# DDR.net
KiCad netlist of a schematic drawn in Altium Designer
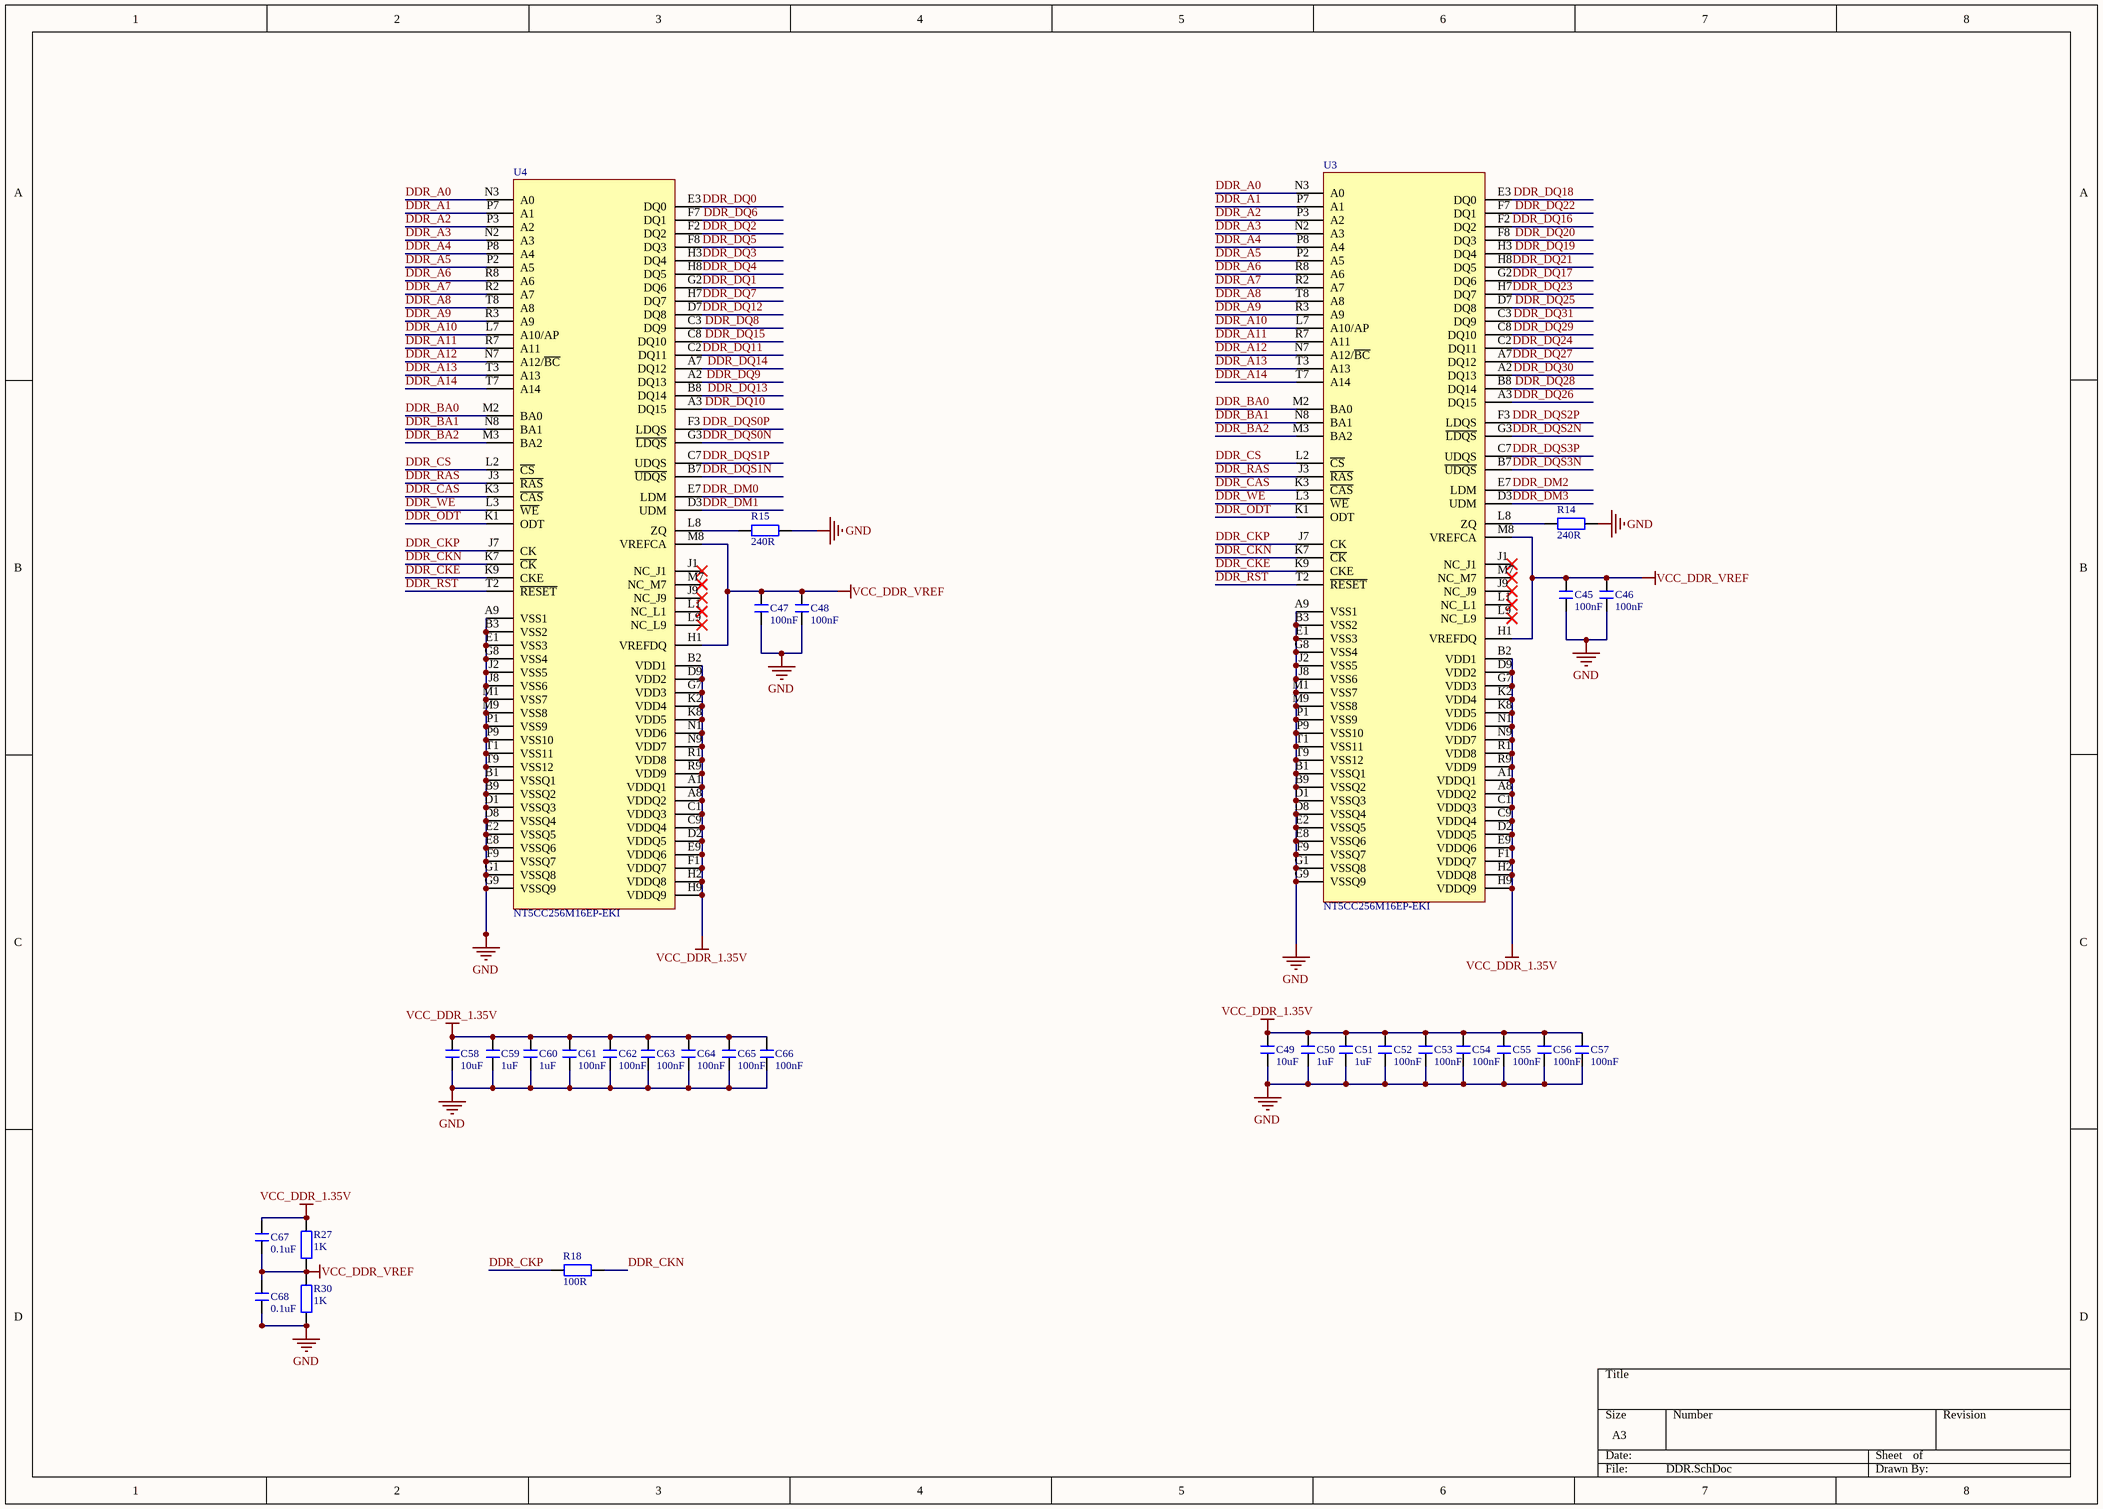
[diagram p0: DDR.SchDoc]

(export (version "E")
  (design (tool "Eeschema 10.0.6"))
  (components
    (comp (ref "C45")
      (value "100nF")
      (footprint "C 0402")
      (description "无极性贴片电容")
      (fields (field (name "版权归属") "正点原子"))
      (libsource (lib "20240511") (part "C"))
    )
    (comp (ref "C46")
      (value "100nF")
      (footprint "C 0402")
      (description "无极性贴片电容")
      (fields (field (name "版权归属") "正点原子"))
      (libsource (lib "20240511") (part "C"))
    )
    (comp (ref "C47")
      (value "100nF")
      (footprint "C 0402")
      (description "无极性贴片电容")
      (fields (field (name "版权归属") "正点原子"))
      (libsource (lib "20240511") (part "C"))
    )
    (comp (ref "C48")
      (value "100nF")
      (footprint "C 0402")
      (description "无极性贴片电容")
      (fields (field (name "版权归属") "正点原子"))
      (libsource (lib "20240511") (part "C"))
    )
    (comp (ref "C49")
      (value "10uF")
      (footprint "C 0603")
      (description "无极性贴片电容")
      (fields (field (name "版权归属") "正点原子"))
      (libsource (lib "20240511") (part "C"))
    )
    (comp (ref "C50")
      (value "1uF")
      (footprint "C 0402")
      (description "无极性贴片电容")
      (fields (field (name "版权归属") "正点原子"))
      (libsource (lib "20240511") (part "C"))
    )
    (comp (ref "C51")
      (value "1uF")
      (footprint "C 0402")
      (description "无极性贴片电容")
      (fields (field (name "版权归属") "正点原子"))
      (libsource (lib "20240511") (part "C"))
    )
    (comp (ref "C52")
      (value "100nF")
      (footprint "C 0402")
      (description "无极性贴片电容")
      (fields (field (name "版权归属") "正点原子"))
      (libsource (lib "20240511") (part "C"))
    )
    (comp (ref "C53")
      (value "100nF")
      (footprint "C 0402")
      (description "无极性贴片电容")
      (fields (field (name "版权归属") "正点原子"))
      (libsource (lib "20240511") (part "C"))
    )
    (comp (ref "C54")
      (value "100nF")
      (footprint "C 0402")
      (description "无极性贴片电容")
      (fields (field (name "版权归属") "正点原子"))
      (libsource (lib "20240511") (part "C"))
    )
    (comp (ref "C55")
      (value "100nF")
      (footprint "C 0402")
      (description "无极性贴片电容")
      (fields (field (name "版权归属") "正点原子"))
      (libsource (lib "20240511") (part "C"))
    )
    (comp (ref "C56")
      (value "100nF")
      (footprint "C 0402")
      (description "无极性贴片电容")
      (fields (field (name "版权归属") "正点原子"))
      (libsource (lib "20240511") (part "C"))
    )
    (comp (ref "C57")
      (value "100nF")
      (footprint "C 0402")
      (description "无极性贴片电容")
      (fields (field (name "版权归属") "正点原子"))
      (libsource (lib "20240511") (part "C"))
    )
    (comp (ref "C58")
      (value "10uF")
      (footprint "C 0603")
      (description "无极性贴片电容")
      (fields (field (name "版权归属") "正点原子"))
      (libsource (lib "20240511") (part "C"))
    )
    (comp (ref "C59")
      (value "1uF")
      (footprint "C 0402")
      (description "无极性贴片电容")
      (fields (field (name "版权归属") "正点原子"))
      (libsource (lib "20240511") (part "C"))
    )
    (comp (ref "C60")
      (value "1uF")
      (footprint "C 0402")
      (description "无极性贴片电容")
      (fields (field (name "版权归属") "正点原子"))
      (libsource (lib "20240511") (part "C"))
    )
    (comp (ref "C61")
      (value "100nF")
      (footprint "C 0402")
      (description "无极性贴片电容")
      (fields (field (name "版权归属") "正点原子"))
      (libsource (lib "20240511") (part "C"))
    )
    (comp (ref "C62")
      (value "100nF")
      (footprint "C 0402")
      (description "无极性贴片电容")
      (fields (field (name "版权归属") "正点原子"))
      (libsource (lib "20240511") (part "C"))
    )
    (comp (ref "C63")
      (value "100nF")
      (footprint "C 0402")
      (description "无极性贴片电容")
      (fields (field (name "版权归属") "正点原子"))
      (libsource (lib "20240511") (part "C"))
    )
    (comp (ref "C64")
      (value "100nF")
      (footprint "C 0402")
      (description "无极性贴片电容")
      (fields (field (name "版权归属") "正点原子"))
      (libsource (lib "20240511") (part "C"))
    )
    (comp (ref "C65")
      (value "100nF")
      (footprint "C 0402")
      (description "无极性贴片电容")
      (fields (field (name "版权归属") "正点原子"))
      (libsource (lib "20240511") (part "C"))
    )
    (comp (ref "C66")
      (value "100nF")
      (footprint "C 0402")
      (description "无极性贴片电容")
      (fields (field (name "版权归属") "正点原子"))
      (libsource (lib "20240511") (part "C"))
    )
    (comp (ref "C67")
      (value "0.1uF")
      (footprint "C 0402")
      (description "无极性贴片电容")
      (fields (field (name "版权归属") "正点原子"))
      (libsource (lib "20240511") (part "C"))
    )
    (comp (ref "C68")
      (value "0.1uF")
      (footprint "C 0402")
      (description "无极性贴片电容")
      (fields (field (name "版权归属") "正点原子"))
      (libsource (lib "20240511") (part "C"))
    )
    (comp (ref "R14")
      (value "240R")
      (footprint "R 0402")
      (description "贴片电阻")
      (fields (field (name "版权归属") "正点原子"))
      (libsource (lib "20240511") (part "R"))
    )
    (comp (ref "R15")
      (value "240R")
      (footprint "R 0402")
      (description "贴片电阻")
      (fields (field (name "版权归属") "正点原子"))
      (libsource (lib "20240511") (part "R"))
    )
    (comp (ref "R18")
      (value "100R")
      (footprint "R 0402")
      (description "贴片电阻")
      (fields (field (name "版权归属") "正点原子"))
      (libsource (lib "20240511") (part "R"))
    )
    (comp (ref "R27")
      (value "1K")
      (footprint "R 0402")
      (description "贴片电阻")
      (fields (field (name "版权归属") "正点原子"))
      (libsource (lib "20240511") (part "R"))
    )
    (comp (ref "R30")
      (value "1K")
      (footprint "R 0402")
      (description "贴片电阻")
      (fields (field (name "版权归属") "正点原子"))
      (libsource (lib "20240511") (part "R"))
    )
    (comp (ref "U3")
      (value "NT5CC256M16EP-EKI")
      (footprint "BGA96")
      (libsource (lib "20240511") (part "MT41K256M16TW"))
    )
    (comp (ref "U4")
      (value "NT5CC256M16EP-EKI")
      (footprint "BGA96")
      (libsource (lib "20240511") (part "MT41K256M16TW"))
    )
  )
  (nets
    (net (code "1") (name "/DDR_A0") (class "Default")
      (node (ref "U3") (pin "N3") (pinfunction "A0_N3") (pintype "passive"))
      (node (ref "U4") (pin "N3") (pinfunction "A0_N3") (pintype "passive"))
    )
    (net (code "2") (name "/DDR_A1") (class "Default")
      (node (ref "U3") (pin "P7") (pinfunction "A1_P7") (pintype "passive"))
      (node (ref "U4") (pin "P7") (pinfunction "A1_P7") (pintype "passive"))
    )
    (net (code "3") (name "/DDR_A2") (class "Default")
      (node (ref "U3") (pin "P3") (pinfunction "A2_P3") (pintype "passive"))
      (node (ref "U4") (pin "P3") (pinfunction "A2_P3") (pintype "passive"))
    )
    (net (code "4") (name "/DDR_A3") (class "Default")
      (node (ref "U3") (pin "N2") (pinfunction "A3_N2") (pintype "passive"))
      (node (ref "U4") (pin "N2") (pinfunction "A3_N2") (pintype "passive"))
    )
    (net (code "5") (name "/DDR_A4") (class "Default")
      (node (ref "U3") (pin "P8") (pinfunction "A4_P8") (pintype "passive"))
      (node (ref "U4") (pin "P8") (pinfunction "A4_P8") (pintype "passive"))
    )
    (net (code "6") (name "/DDR_A5") (class "Default")
      (node (ref "U3") (pin "P2") (pinfunction "A5_P2") (pintype "passive"))
      (node (ref "U4") (pin "P2") (pinfunction "A5_P2") (pintype "passive"))
    )
    (net (code "7") (name "/DDR_A6") (class "Default")
      (node (ref "U3") (pin "R8") (pinfunction "A6_R8") (pintype "passive"))
      (node (ref "U4") (pin "R8") (pinfunction "A6_R8") (pintype "passive"))
    )
    (net (code "8") (name "/DDR_A7") (class "Default")
      (node (ref "U3") (pin "R2") (pinfunction "A7_R2") (pintype "passive"))
      (node (ref "U4") (pin "R2") (pinfunction "A7_R2") (pintype "passive"))
    )
    (net (code "9") (name "/DDR_A8") (class "Default")
      (node (ref "U3") (pin "T8") (pinfunction "A8_T8") (pintype "passive"))
      (node (ref "U4") (pin "T8") (pinfunction "A8_T8") (pintype "passive"))
    )
    (net (code "10") (name "/DDR_A9") (class "Default")
      (node (ref "U3") (pin "R3") (pinfunction "A9_R3") (pintype "passive"))
      (node (ref "U4") (pin "R3") (pinfunction "A9_R3") (pintype "passive"))
    )
    (net (code "11") (name "/DDR_A10") (class "Default")
      (node (ref "U3") (pin "L7") (pinfunction "A10/AP_L7") (pintype "passive"))
      (node (ref "U4") (pin "L7") (pinfunction "A10/AP_L7") (pintype "passive"))
    )
    (net (code "12") (name "/DDR_A11") (class "Default")
      (node (ref "U3") (pin "R7") (pinfunction "A11_R7") (pintype "passive"))
      (node (ref "U4") (pin "R7") (pinfunction "A11_R7") (pintype "passive"))
    )
    (net (code "13") (name "/DDR_A12") (class "Default")
      (node (ref "U3") (pin "N7") (pinfunction "A12/~{BC}_N7") (pintype "passive"))
      (node (ref "U4") (pin "N7") (pinfunction "A12/~{BC}_N7") (pintype "passive"))
    )
    (net (code "14") (name "/DDR_A13") (class "Default")
      (node (ref "U3") (pin "T3") (pinfunction "A13_T3") (pintype "passive"))
      (node (ref "U4") (pin "T3") (pinfunction "A13_T3") (pintype "passive"))
    )
    (net (code "15") (name "/DDR_A14") (class "Default")
      (node (ref "U3") (pin "T7") (pinfunction "A14_T7") (pintype "passive"))
      (node (ref "U4") (pin "T7") (pinfunction "A14_T7") (pintype "passive"))
    )
    (net (code "16") (name "/DDR_BA0") (class "Default")
      (node (ref "U3") (pin "M2") (pinfunction "BA0_M2") (pintype "passive"))
      (node (ref "U4") (pin "M2") (pinfunction "BA0_M2") (pintype "passive"))
    )
    (net (code "17") (name "/DDR_BA1") (class "Default")
      (node (ref "U3") (pin "N8") (pinfunction "BA1_N8") (pintype "passive"))
      (node (ref "U4") (pin "N8") (pinfunction "BA1_N8") (pintype "passive"))
    )
    (net (code "18") (name "/DDR_BA2") (class "Default")
      (node (ref "U3") (pin "M3") (pinfunction "BA2_M3") (pintype "passive"))
      (node (ref "U4") (pin "M3") (pinfunction "BA2_M3") (pintype "passive"))
    )
    (net (code "19") (name "/DDR_CAS") (class "Default")
      (node (ref "U3") (pin "K3") (pinfunction "~{CAS}_K3") (pintype "passive"))
      (node (ref "U4") (pin "K3") (pinfunction "~{CAS}_K3") (pintype "passive"))
    )
    (net (code "20") (name "/DDR_CKE") (class "Default")
      (node (ref "U3") (pin "K9") (pinfunction "CKE_K9") (pintype "passive"))
      (node (ref "U4") (pin "K9") (pinfunction "CKE_K9") (pintype "passive"))
    )
    (net (code "21") (name "/DDR_CKN") (class "Default")
      (node (ref "R18") (pin "1") (pinfunction "1_1") (pintype "passive"))
      (node (ref "U3") (pin "K7") (pinfunction "~{CK}_K7") (pintype "passive"))
      (node (ref "U4") (pin "K7") (pinfunction "~{CK}_K7") (pintype "passive"))
    )
    (net (code "22") (name "/DDR_CKP") (class "Default")
      (node (ref "R18") (pin "2") (pinfunction "2_2") (pintype "passive"))
      (node (ref "U3") (pin "J7") (pinfunction "CK_J7") (pintype "passive"))
      (node (ref "U4") (pin "J7") (pinfunction "CK_J7") (pintype "passive"))
    )
    (net (code "23") (name "/DDR_CS") (class "Default")
      (node (ref "U3") (pin "L2") (pinfunction "~{CS}_L2") (pintype "passive"))
      (node (ref "U4") (pin "L2") (pinfunction "~{CS}_L2") (pintype "passive"))
    )
    (net (code "24") (name "/DDR_DM0") (class "Default")
      (node (ref "U4") (pin "E7") (pinfunction "LDM_E7") (pintype "passive"))
    )
    (net (code "25") (name "/DDR_DM1") (class "Default")
      (node (ref "U4") (pin "D3") (pinfunction "UDM_D3") (pintype "passive"))
    )
    (net (code "26") (name "/DDR_DM2") (class "Default")
      (node (ref "U3") (pin "E7") (pinfunction "LDM_E7") (pintype "passive"))
    )
    (net (code "27") (name "/DDR_DM3") (class "Default")
      (node (ref "U3") (pin "D3") (pinfunction "UDM_D3") (pintype "passive"))
    )
    (net (code "28") (name "/DDR_DQ0") (class "Default")
      (node (ref "U4") (pin "E3") (pinfunction "DQ0_E3") (pintype "passive"))
    )
    (net (code "29") (name "/DDR_DQ1") (class "Default")
      (node (ref "U4") (pin "G2") (pinfunction "DQ6_G2") (pintype "passive"))
    )
    (net (code "30") (name "/DDR_DQ2") (class "Default")
      (node (ref "U4") (pin "F2") (pinfunction "DQ2_F2") (pintype "passive"))
    )
    (net (code "31") (name "/DDR_DQ3") (class "Default")
      (node (ref "U4") (pin "H3") (pinfunction "DQ4_H3") (pintype "passive"))
    )
    (net (code "32") (name "/DDR_DQ4") (class "Default")
      (node (ref "U4") (pin "H8") (pinfunction "DQ5_H8") (pintype "passive"))
    )
    (net (code "33") (name "/DDR_DQ5") (class "Default")
      (node (ref "U4") (pin "F8") (pinfunction "DQ3_F8") (pintype "passive"))
    )
    (net (code "34") (name "/DDR_DQ6") (class "Default")
      (node (ref "U4") (pin "F7") (pinfunction "DQ1_F7") (pintype "passive"))
    )
    (net (code "35") (name "/DDR_DQ7") (class "Default")
      (node (ref "U4") (pin "H7") (pinfunction "DQ7_H7") (pintype "passive"))
    )
    (net (code "36") (name "/DDR_DQ8") (class "Default")
      (node (ref "U4") (pin "C3") (pinfunction "DQ9_C3") (pintype "passive"))
    )
    (net (code "37") (name "/DDR_DQ9") (class "Default")
      (node (ref "U4") (pin "A2") (pinfunction "DQ13_A2") (pintype "passive"))
    )
    (net (code "38") (name "/DDR_DQ10") (class "Default")
      (node (ref "U4") (pin "A3") (pinfunction "DQ15_A3") (pintype "passive"))
    )
    (net (code "39") (name "/DDR_DQ11") (class "Default")
      (node (ref "U4") (pin "C2") (pinfunction "DQ11_C2") (pintype "passive"))
    )
    (net (code "40") (name "/DDR_DQ12") (class "Default")
      (node (ref "U4") (pin "D7") (pinfunction "DQ8_D7") (pintype "passive"))
    )
    (net (code "41") (name "/DDR_DQ13") (class "Default")
      (node (ref "U4") (pin "B8") (pinfunction "DQ14_B8") (pintype "passive"))
    )
    (net (code "42") (name "/DDR_DQ14") (class "Default")
      (node (ref "U4") (pin "A7") (pinfunction "DQ12_A7") (pintype "passive"))
    )
    (net (code "43") (name "/DDR_DQ15") (class "Default")
      (node (ref "U4") (pin "C8") (pinfunction "DQ10_C8") (pintype "passive"))
    )
    (net (code "44") (name "/DDR_DQ16") (class "Default")
      (node (ref "U3") (pin "F2") (pinfunction "DQ2_F2") (pintype "passive"))
    )
    (net (code "45") (name "/DDR_DQ17") (class "Default")
      (node (ref "U3") (pin "G2") (pinfunction "DQ6_G2") (pintype "passive"))
    )
    (net (code "46") (name "/DDR_DQ18") (class "Default")
      (node (ref "U3") (pin "E3") (pinfunction "DQ0_E3") (pintype "passive"))
    )
    (net (code "47") (name "/DDR_DQ19") (class "Default")
      (node (ref "U3") (pin "H3") (pinfunction "DQ4_H3") (pintype "passive"))
    )
    (net (code "48") (name "/DDR_DQ20") (class "Default")
      (node (ref "U3") (pin "F8") (pinfunction "DQ3_F8") (pintype "passive"))
    )
    (net (code "49") (name "/DDR_DQ21") (class "Default")
      (node (ref "U3") (pin "H8") (pinfunction "DQ5_H8") (pintype "passive"))
    )
    (net (code "50") (name "/DDR_DQ22") (class "Default")
      (node (ref "U3") (pin "F7") (pinfunction "DQ1_F7") (pintype "passive"))
    )
    (net (code "51") (name "/DDR_DQ23") (class "Default")
      (node (ref "U3") (pin "H7") (pinfunction "DQ7_H7") (pintype "passive"))
    )
    (net (code "52") (name "/DDR_DQ24") (class "Default")
      (node (ref "U3") (pin "C2") (pinfunction "DQ11_C2") (pintype "passive"))
    )
    (net (code "53") (name "/DDR_DQ25") (class "Default")
      (node (ref "U3") (pin "D7") (pinfunction "DQ8_D7") (pintype "passive"))
    )
    (net (code "54") (name "/DDR_DQ26") (class "Default")
      (node (ref "U3") (pin "A3") (pinfunction "DQ15_A3") (pintype "passive"))
    )
    (net (code "55") (name "/DDR_DQ27") (class "Default")
      (node (ref "U3") (pin "A7") (pinfunction "DQ12_A7") (pintype "passive"))
    )
    (net (code "56") (name "/DDR_DQ28") (class "Default")
      (node (ref "U3") (pin "B8") (pinfunction "DQ14_B8") (pintype "passive"))
    )
    (net (code "57") (name "/DDR_DQ29") (class "Default")
      (node (ref "U3") (pin "C8") (pinfunction "DQ10_C8") (pintype "passive"))
    )
    (net (code "58") (name "/DDR_DQ30") (class "Default")
      (node (ref "U3") (pin "A2") (pinfunction "DQ13_A2") (pintype "passive"))
    )
    (net (code "59") (name "/DDR_DQ31") (class "Default")
      (node (ref "U3") (pin "C3") (pinfunction "DQ9_C3") (pintype "passive"))
    )
    (net (code "60") (name "/DDR_DQS0N") (class "Default")
      (node (ref "U4") (pin "G3") (pinfunction "~{LDQS}_G3") (pintype "passive"))
    )
    (net (code "61") (name "/DDR_DQS0P") (class "Default")
      (node (ref "U4") (pin "F3") (pinfunction "LDQS_F3") (pintype "passive"))
    )
    (net (code "62") (name "/DDR_DQS1N") (class "Default")
      (node (ref "U4") (pin "B7") (pinfunction "~{UDQS}_B7") (pintype "passive"))
    )
    (net (code "63") (name "/DDR_DQS1P") (class "Default")
      (node (ref "U4") (pin "C7") (pinfunction "UDQS_C7") (pintype "passive"))
    )
    (net (code "64") (name "/DDR_DQS2N") (class "Default")
      (node (ref "U3") (pin "G3") (pinfunction "~{LDQS}_G3") (pintype "passive"))
    )
    (net (code "65") (name "/DDR_DQS2P") (class "Default")
      (node (ref "U3") (pin "F3") (pinfunction "LDQS_F3") (pintype "passive"))
    )
    (net (code "66") (name "/DDR_DQS3N") (class "Default")
      (node (ref "U3") (pin "B7") (pinfunction "~{UDQS}_B7") (pintype "passive"))
    )
    (net (code "67") (name "/DDR_DQS3P") (class "Default")
      (node (ref "U3") (pin "C7") (pinfunction "UDQS_C7") (pintype "passive"))
    )
    (net (code "68") (name "/DDR_ODT") (class "Default")
      (node (ref "U3") (pin "K1") (pinfunction "ODT_K1") (pintype "passive"))
      (node (ref "U4") (pin "K1") (pinfunction "ODT_K1") (pintype "passive"))
    )
    (net (code "69") (name "/DDR_RAS") (class "Default")
      (node (ref "U3") (pin "J3") (pinfunction "~{RAS}_J3") (pintype "passive"))
      (node (ref "U4") (pin "J3") (pinfunction "~{RAS}_J3") (pintype "passive"))
    )
    (net (code "70") (name "/DDR_RST") (class "Default")
      (node (ref "U3") (pin "T2") (pinfunction "~{RESET}_T2") (pintype "passive"))
      (node (ref "U4") (pin "T2") (pinfunction "~{RESET}_T2") (pintype "passive"))
    )
    (net (code "71") (name "/DDR_WE") (class "Default")
      (node (ref "U3") (pin "L3") (pinfunction "~{WE}_L3") (pintype "passive"))
      (node (ref "U4") (pin "L3") (pinfunction "~{WE}_L3") (pintype "passive"))
    )
    (net (code "72") (name "GND") (class "Default")
      (node (ref "C45") (pin "1") (pinfunction "1_1") (pintype "passive"))
      (node (ref "C46") (pin "1") (pinfunction "1_1") (pintype "passive"))
      (node (ref "C47") (pin "1") (pinfunction "1_1") (pintype "passive"))
      (node (ref "C48") (pin "1") (pinfunction "1_1") (pintype "passive"))
      (node (ref "C49") (pin "1") (pinfunction "1_1") (pintype "passive"))
      (node (ref "C50") (pin "1") (pinfunction "1_1") (pintype "passive"))
      (node (ref "C51") (pin "1") (pinfunction "1_1") (pintype "passive"))
      (node (ref "C52") (pin "1") (pinfunction "1_1") (pintype "passive"))
      (node (ref "C53") (pin "1") (pinfunction "1_1") (pintype "passive"))
      (node (ref "C54") (pin "1") (pinfunction "1_1") (pintype "passive"))
      (node (ref "C55") (pin "1") (pinfunction "1_1") (pintype "passive"))
      (node (ref "C56") (pin "1") (pinfunction "1_1") (pintype "passive"))
      (node (ref "C57") (pin "1") (pinfunction "1_1") (pintype "passive"))
      (node (ref "C58") (pin "1") (pinfunction "1_1") (pintype "passive"))
      (node (ref "C59") (pin "1") (pinfunction "1_1") (pintype "passive"))
      (node (ref "C60") (pin "1") (pinfunction "1_1") (pintype "passive"))
      (node (ref "C61") (pin "1") (pinfunction "1_1") (pintype "passive"))
      (node (ref "C62") (pin "1") (pinfunction "1_1") (pintype "passive"))
      (node (ref "C63") (pin "1") (pinfunction "1_1") (pintype "passive"))
      (node (ref "C64") (pin "1") (pinfunction "1_1") (pintype "passive"))
      (node (ref "C65") (pin "1") (pinfunction "1_1") (pintype "passive"))
      (node (ref "C66") (pin "1") (pinfunction "1_1") (pintype "passive"))
      (node (ref "C68") (pin "1") (pinfunction "1_1") (pintype "passive"))
      (node (ref "R14") (pin "2") (pinfunction "2_2") (pintype "passive"))
      (node (ref "R15") (pin "2") (pinfunction "2_2") (pintype "passive"))
      (node (ref "R30") (pin "1") (pinfunction "1_1") (pintype "passive"))
      (node (ref "U3") (pin "A9") (pinfunction "VSS1_A9") (pintype "passive"))
      (node (ref "U3") (pin "B1") (pinfunction "VSSQ1_B1") (pintype "passive"))
      (node (ref "U3") (pin "B3") (pinfunction "VSS2_B3") (pintype "passive"))
      (node (ref "U3") (pin "B9") (pinfunction "VSSQ2_B9") (pintype "passive"))
      (node (ref "U3") (pin "D1") (pinfunction "VSSQ3_D1") (pintype "passive"))
      (node (ref "U3") (pin "D8") (pinfunction "VSSQ4_D8") (pintype "passive"))
      (node (ref "U3") (pin "E1") (pinfunction "VSS3_E1") (pintype "passive"))
      (node (ref "U3") (pin "E2") (pinfunction "VSSQ5_E2") (pintype "passive"))
      (node (ref "U3") (pin "E8") (pinfunction "VSSQ6_E8") (pintype "passive"))
      (node (ref "U3") (pin "F9") (pinfunction "VSSQ7_F9") (pintype "passive"))
      (node (ref "U3") (pin "G1") (pinfunction "VSSQ8_G1") (pintype "passive"))
      (node (ref "U3") (pin "G8") (pinfunction "VSS4_G8") (pintype "passive"))
      (node (ref "U3") (pin "G9") (pinfunction "VSSQ9_G9") (pintype "passive"))
      (node (ref "U3") (pin "J2") (pinfunction "VSS5_J2") (pintype "passive"))
      (node (ref "U3") (pin "J8") (pinfunction "VSS6_J8") (pintype "passive"))
      (node (ref "U3") (pin "M1") (pinfunction "VSS7_M1") (pintype "passive"))
      (node (ref "U3") (pin "M9") (pinfunction "VSS8_M9") (pintype "passive"))
      (node (ref "U3") (pin "P1") (pinfunction "VSS9_P1") (pintype "passive"))
      (node (ref "U3") (pin "P9") (pinfunction "VSS10_P9") (pintype "passive"))
      (node (ref "U3") (pin "T1") (pinfunction "VSS11_T1") (pintype "passive"))
      (node (ref "U3") (pin "T9") (pinfunction "VSS12_T9") (pintype "passive"))
      (node (ref "U4") (pin "A9") (pinfunction "VSS1_A9") (pintype "passive"))
      (node (ref "U4") (pin "B1") (pinfunction "VSSQ1_B1") (pintype "passive"))
      (node (ref "U4") (pin "B3") (pinfunction "VSS2_B3") (pintype "passive"))
      (node (ref "U4") (pin "B9") (pinfunction "VSSQ2_B9") (pintype "passive"))
      (node (ref "U4") (pin "D1") (pinfunction "VSSQ3_D1") (pintype "passive"))
      (node (ref "U4") (pin "D8") (pinfunction "VSSQ4_D8") (pintype "passive"))
      (node (ref "U4") (pin "E1") (pinfunction "VSS3_E1") (pintype "passive"))
      (node (ref "U4") (pin "E2") (pinfunction "VSSQ5_E2") (pintype "passive"))
      (node (ref "U4") (pin "E8") (pinfunction "VSSQ6_E8") (pintype "passive"))
      (node (ref "U4") (pin "F9") (pinfunction "VSSQ7_F9") (pintype "passive"))
      (node (ref "U4") (pin "G1") (pinfunction "VSSQ8_G1") (pintype "passive"))
      (node (ref "U4") (pin "G8") (pinfunction "VSS4_G8") (pintype "passive"))
      (node (ref "U4") (pin "G9") (pinfunction "VSSQ9_G9") (pintype "passive"))
      (node (ref "U4") (pin "J2") (pinfunction "VSS5_J2") (pintype "passive"))
      (node (ref "U4") (pin "J8") (pinfunction "VSS6_J8") (pintype "passive"))
      (node (ref "U4") (pin "M1") (pinfunction "VSS7_M1") (pintype "passive"))
      (node (ref "U4") (pin "M9") (pinfunction "VSS8_M9") (pintype "passive"))
      (node (ref "U4") (pin "P1") (pinfunction "VSS9_P1") (pintype "passive"))
      (node (ref "U4") (pin "P9") (pinfunction "VSS10_P9") (pintype "passive"))
      (node (ref "U4") (pin "T1") (pinfunction "VSS11_T1") (pintype "passive"))
      (node (ref "U4") (pin "T9") (pinfunction "VSS12_T9") (pintype "passive"))
    )
    (net (code "73") (name "Net-(U3-ZQ)") (class "Default")
      (node (ref "R14") (pin "1") (pinfunction "1_1") (pintype "passive"))
      (node (ref "U3") (pin "L8") (pinfunction "ZQ_L8") (pintype "passive"))
    )
    (net (code "74") (name "Net-(U4-ZQ)") (class "Default")
      (node (ref "R15") (pin "1") (pinfunction "1_1") (pintype "passive"))
      (node (ref "U4") (pin "L8") (pinfunction "ZQ_L8") (pintype "passive"))
    )
    (net (code "75") (name "VCC_DDR_1.35V") (class "Default")
      (node (ref "C49") (pin "2") (pinfunction "2_2") (pintype "passive"))
      (node (ref "C50") (pin "2") (pinfunction "2_2") (pintype "passive"))
      (node (ref "C51") (pin "2") (pinfunction "2_2") (pintype "passive"))
      (node (ref "C52") (pin "2") (pinfunction "2_2") (pintype "passive"))
      (node (ref "C53") (pin "2") (pinfunction "2_2") (pintype "passive"))
      (node (ref "C54") (pin "2") (pinfunction "2_2") (pintype "passive"))
      (node (ref "C55") (pin "2") (pinfunction "2_2") (pintype "passive"))
      (node (ref "C56") (pin "2") (pinfunction "2_2") (pintype "passive"))
      (node (ref "C57") (pin "2") (pinfunction "2_2") (pintype "passive"))
      (node (ref "C58") (pin "2") (pinfunction "2_2") (pintype "passive"))
      (node (ref "C59") (pin "2") (pinfunction "2_2") (pintype "passive"))
      (node (ref "C60") (pin "2") (pinfunction "2_2") (pintype "passive"))
      (node (ref "C61") (pin "2") (pinfunction "2_2") (pintype "passive"))
      (node (ref "C62") (pin "2") (pinfunction "2_2") (pintype "passive"))
      (node (ref "C63") (pin "2") (pinfunction "2_2") (pintype "passive"))
      (node (ref "C64") (pin "2") (pinfunction "2_2") (pintype "passive"))
      (node (ref "C65") (pin "2") (pinfunction "2_2") (pintype "passive"))
      (node (ref "C66") (pin "2") (pinfunction "2_2") (pintype "passive"))
      (node (ref "C67") (pin "2") (pinfunction "2_2") (pintype "passive"))
      (node (ref "R27") (pin "2") (pinfunction "2_2") (pintype "passive"))
      (node (ref "U3") (pin "A1") (pinfunction "VDDQ1_A1") (pintype "passive"))
      (node (ref "U3") (pin "A8") (pinfunction "VDDQ2_A8") (pintype "passive"))
      (node (ref "U3") (pin "B2") (pinfunction "VDD1_B2") (pintype "passive"))
      (node (ref "U3") (pin "C1") (pinfunction "VDDQ3_C1") (pintype "passive"))
      (node (ref "U3") (pin "C9") (pinfunction "VDDQ4_C9") (pintype "passive"))
      (node (ref "U3") (pin "D2") (pinfunction "VDDQ5_D2") (pintype "passive"))
      (node (ref "U3") (pin "D9") (pinfunction "VDD2_D9") (pintype "passive"))
      (node (ref "U3") (pin "E9") (pinfunction "VDDQ6_E9") (pintype "passive"))
      (node (ref "U3") (pin "F1") (pinfunction "VDDQ7_F1") (pintype "passive"))
      (node (ref "U3") (pin "G7") (pinfunction "VDD3_G7") (pintype "passive"))
      (node (ref "U3") (pin "H2") (pinfunction "VDDQ8_H2") (pintype "passive"))
      (node (ref "U3") (pin "H9") (pinfunction "VDDQ9_H9") (pintype "passive"))
      (node (ref "U3") (pin "K2") (pinfunction "VDD4_K2") (pintype "passive"))
      (node (ref "U3") (pin "K8") (pinfunction "VDD5_K8") (pintype "passive"))
      (node (ref "U3") (pin "N1") (pinfunction "VDD6_N1") (pintype "passive"))
      (node (ref "U3") (pin "N9") (pinfunction "VDD7_N9") (pintype "passive"))
      (node (ref "U3") (pin "R1") (pinfunction "VDD8_R1") (pintype "passive"))
      (node (ref "U3") (pin "R9") (pinfunction "VDD9_R9") (pintype "passive"))
      (node (ref "U4") (pin "A1") (pinfunction "VDDQ1_A1") (pintype "passive"))
      (node (ref "U4") (pin "A8") (pinfunction "VDDQ2_A8") (pintype "passive"))
      (node (ref "U4") (pin "B2") (pinfunction "VDD1_B2") (pintype "passive"))
      (node (ref "U4") (pin "C1") (pinfunction "VDDQ3_C1") (pintype "passive"))
      (node (ref "U4") (pin "C9") (pinfunction "VDDQ4_C9") (pintype "passive"))
      (node (ref "U4") (pin "D2") (pinfunction "VDDQ5_D2") (pintype "passive"))
      (node (ref "U4") (pin "D9") (pinfunction "VDD2_D9") (pintype "passive"))
      (node (ref "U4") (pin "E9") (pinfunction "VDDQ6_E9") (pintype "passive"))
      (node (ref "U4") (pin "F1") (pinfunction "VDDQ7_F1") (pintype "passive"))
      (node (ref "U4") (pin "G7") (pinfunction "VDD3_G7") (pintype "passive"))
      (node (ref "U4") (pin "H2") (pinfunction "VDDQ8_H2") (pintype "passive"))
      (node (ref "U4") (pin "H9") (pinfunction "VDDQ9_H9") (pintype "passive"))
      (node (ref "U4") (pin "K2") (pinfunction "VDD4_K2") (pintype "passive"))
      (node (ref "U4") (pin "K8") (pinfunction "VDD5_K8") (pintype "passive"))
      (node (ref "U4") (pin "N1") (pinfunction "VDD6_N1") (pintype "passive"))
      (node (ref "U4") (pin "N9") (pinfunction "VDD7_N9") (pintype "passive"))
      (node (ref "U4") (pin "R1") (pinfunction "VDD8_R1") (pintype "passive"))
      (node (ref "U4") (pin "R9") (pinfunction "VDD9_R9") (pintype "passive"))
    )
    (net (code "76") (name "VCC_DDR_VREF") (class "Default")
      (node (ref "C45") (pin "2") (pinfunction "2_2") (pintype "passive"))
      (node (ref "C46") (pin "2") (pinfunction "2_2") (pintype "passive"))
      (node (ref "C47") (pin "2") (pinfunction "2_2") (pintype "passive"))
      (node (ref "C48") (pin "2") (pinfunction "2_2") (pintype "passive"))
      (node (ref "C67") (pin "1") (pinfunction "1_1") (pintype "passive"))
      (node (ref "C68") (pin "2") (pinfunction "2_2") (pintype "passive"))
      (node (ref "R27") (pin "1") (pinfunction "1_1") (pintype "passive"))
      (node (ref "R30") (pin "2") (pinfunction "2_2") (pintype "passive"))
      (node (ref "U3") (pin "H1") (pinfunction "VREFDQ_H1") (pintype "passive"))
      (node (ref "U3") (pin "M8") (pinfunction "VREFCA_M8") (pintype "passive"))
      (node (ref "U4") (pin "H1") (pinfunction "VREFDQ_H1") (pintype "passive"))
      (node (ref "U4") (pin "M8") (pinfunction "VREFCA_M8") (pintype "passive"))
    )
    (net (code "77") (name "unconnected-(U3-NC_J1-PadJ1)") (class "Default")
      (node (ref "U3") (pin "J1") (pinfunction "NC_J1_J1") (pintype "passive+no_connect"))
    )
    (net (code "78") (name "unconnected-(U3-NC_J9-PadJ9)") (class "Default")
      (node (ref "U3") (pin "J9") (pinfunction "NC_J9_J9") (pintype "passive+no_connect"))
    )
    (net (code "79") (name "unconnected-(U3-NC_L1-PadL1)") (class "Default")
      (node (ref "U3") (pin "L1") (pinfunction "NC_L1_L1") (pintype "passive+no_connect"))
    )
    (net (code "80") (name "unconnected-(U3-NC_L9-PadL9)") (class "Default")
      (node (ref "U3") (pin "L9") (pinfunction "NC_L9_L9") (pintype "passive+no_connect"))
    )
    (net (code "81") (name "unconnected-(U3-NC_M7-PadM7)") (class "Default")
      (node (ref "U3") (pin "M7") (pinfunction "NC_M7_M7") (pintype "passive+no_connect"))
    )
    (net (code "82") (name "unconnected-(U4-NC_J1-PadJ1)") (class "Default")
      (node (ref "U4") (pin "J1") (pinfunction "NC_J1_J1") (pintype "passive+no_connect"))
    )
    (net (code "83") (name "unconnected-(U4-NC_J9-PadJ9)") (class "Default")
      (node (ref "U4") (pin "J9") (pinfunction "NC_J9_J9") (pintype "passive+no_connect"))
    )
    (net (code "84") (name "unconnected-(U4-NC_L1-PadL1)") (class "Default")
      (node (ref "U4") (pin "L1") (pinfunction "NC_L1_L1") (pintype "passive+no_connect"))
    )
    (net (code "85") (name "unconnected-(U4-NC_L9-PadL9)") (class "Default")
      (node (ref "U4") (pin "L9") (pinfunction "NC_L9_L9") (pintype "passive+no_connect"))
    )
    (net (code "86") (name "unconnected-(U4-NC_M7-PadM7)") (class "Default")
      (node (ref "U4") (pin "M7") (pinfunction "NC_M7_M7") (pintype "passive+no_connect"))
    )
  )
)
